# Boost_Converter.net
KiCad netlist of a schematic drawn in Altium Designer
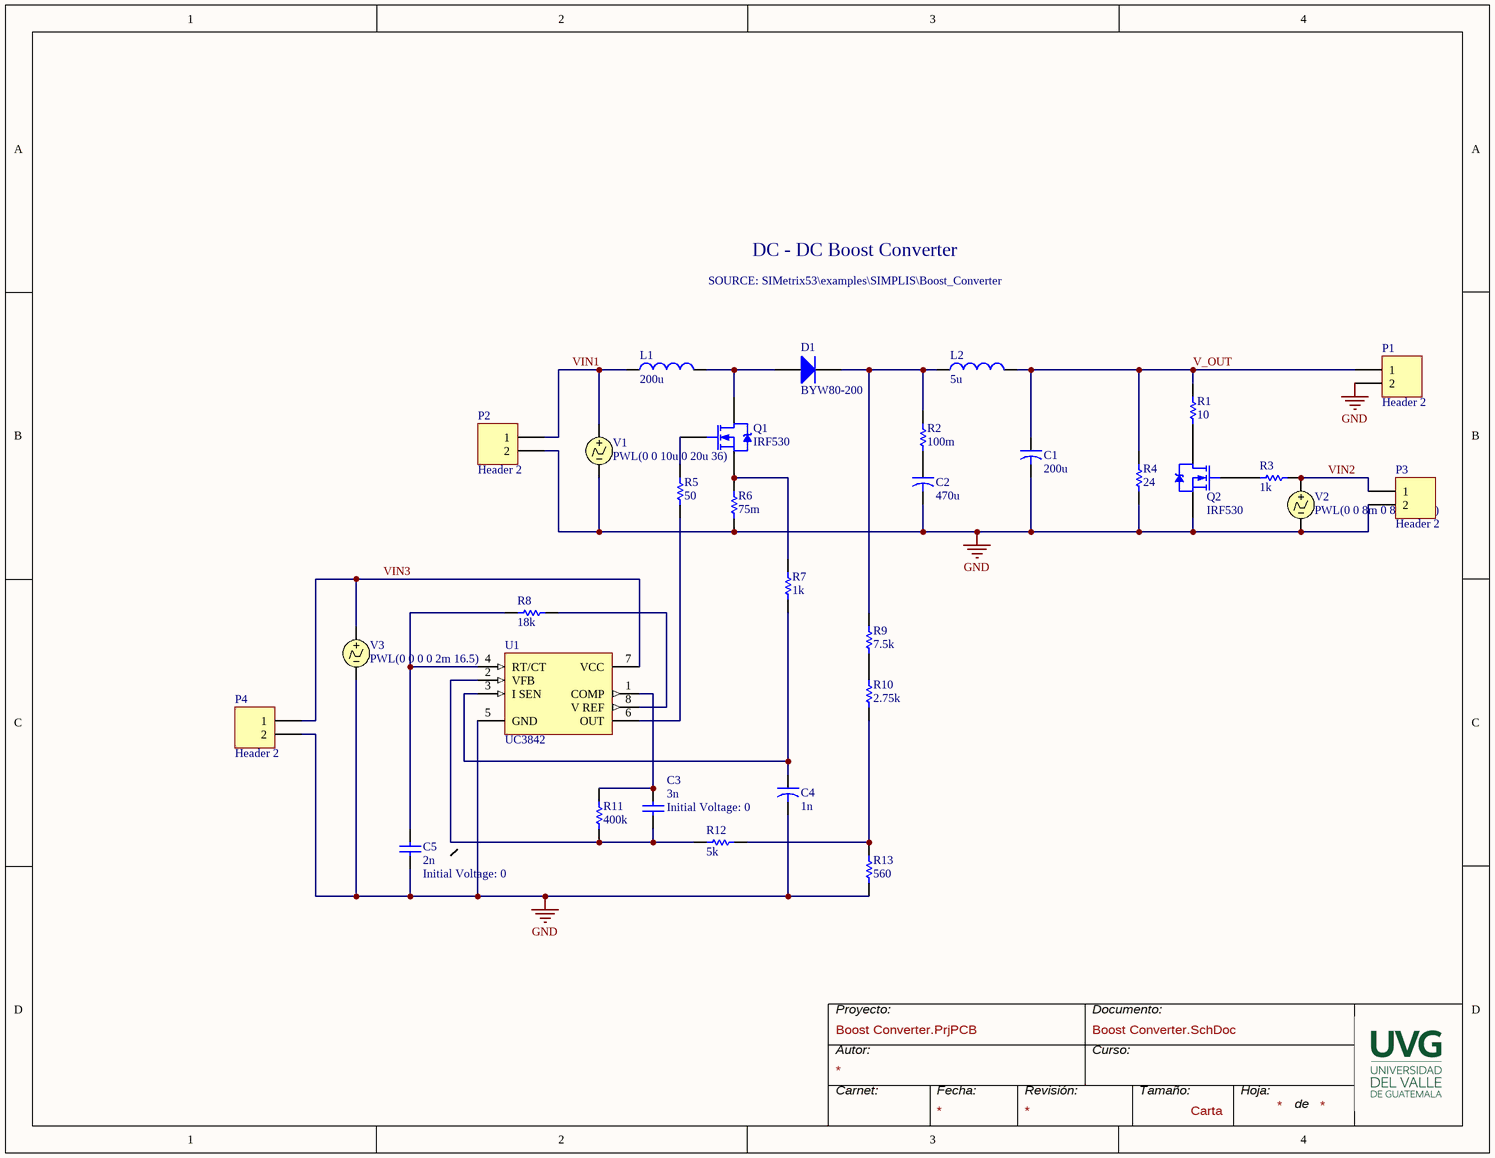
[diagram p0: Boost Converter.SchDoc]

(export (version "E")
  (design (tool "Eeschema 10.0.6"))
  (components
    (comp (ref "C1")
      (value "Cap Elec (L1-3)")
      (footprint "CAPR5-4X5")
      (description "Electrolytic Capacitor (Levels 1-3)")
      (fields (field (name "CC") "200u") (field (name "PUBLISHER") "Altium Limited"))
      (libsource (lib "SIMetrix Devices") (part "Cap Elec (L1-3)"))
    )
    (comp (ref "C2")
      (value "Cap Elec (L1-3)")
      (footprint "CAPR5-4X5")
      (description "Electrolytic Capacitor (Levels 1-3)")
      (fields (field (name "CC") "470u") (field (name "PUBLISHER") "Altium Limited"))
      (libsource (lib "SIMetrix Devices") (part "Cap Elec (L1-3)"))
    )
    (comp (ref "C3")
      (value "3n")
      (footprint "RAD-0.1")
      (description "Capacitor")
      (fields
        (field (name "INITIAL VOLTAGE") "0")
        (field (name "Comment") "Cap")
        (field (name "PUBLISHER") "Altium Limited")
      )
      (libsource (lib "Miscellaneous Devices") (part "Cap"))
    )
    (comp (ref "C4")
      (value "Cap Elec (L1-3)")
      (footprint "CAPR5-4X5")
      (description "Electrolytic Capacitor (Levels 1-3)")
      (fields (field (name "CC") "1n") (field (name "PUBLISHER") "Altium Limited"))
      (libsource (lib "SIMetrix Devices") (part "Cap Elec (L1-3)"))
    )
    (comp (ref "C5")
      (value "2n")
      (footprint "RAD-0.1")
      (description "Capacitor")
      (fields
        (field (name "INITIAL VOLTAGE") "0")
        (field (name "Comment") "Cap")
        (field (name "PUBLISHER") "Altium Limited")
      )
      (libsource (lib "Miscellaneous Devices") (part "Cap"))
    )
    (comp (ref "D1")
      (value "BYW80-200")
      (footprint "SMC")
      (description "High-Efficiency Fast Recovery Rectifier Diode")
      (fields (field (name "PUBLISHER") "Altium Limited"))
      (libsource (lib "SIMetrix Devices") (part "BYW80-200"))
    )
    (comp (ref "L1")
      (value "200u")
      (footprint "RAD")
      (description "Lossy Inductor")
      (fields (field (name "PUBLISHER") "Altium Limited"))
      (libsource (lib "SIMetrix Devices") (part "Inductor (Lossy)"))
    )
    (comp (ref "L2")
      (value "5u")
      (footprint "0402-A")
      (description "Lossy Inductor")
      (fields (field (name "PUBLISHER") "Altium Limited"))
      (libsource (lib "SIMetrix Devices") (part "Inductor (Lossy)"))
    )
    (comp (ref "P1")
      (value "Header 2")
      (footprint "HDR1X2")
      (description "Header, 2-Pin")
      (fields (field (name "PUBLISHER") "Altium Limited"))
      (libsource (lib "") (part "Header 2_1"))
    )
    (comp (ref "P2")
      (value "Header 2")
      (footprint "HDR1X2")
      (description "Header, 2-Pin")
      (fields (field (name "PUBLISHER") "Altium Limited"))
      (libsource (lib "Miscellaneous Connectors") (part "Header 2"))
    )
    (comp (ref "P3")
      (value "Header 2")
      (footprint "HDR1X2")
      (description "Header, 2-Pin")
      (fields (field (name "PUBLISHER") "Altium Limited"))
      (libsource (lib "") (part "Header 2_1"))
    )
    (comp (ref "P4")
      (value "Header 2")
      (footprint "HDR1X2")
      (description "Header, 2-Pin")
      (fields (field (name "PUBLISHER") "Altium Limited"))
      (libsource (lib "Miscellaneous Connectors") (part "Header 2"))
    )
    (comp (ref "Q1")
      (value "IRF530")
      (footprint "TO-220AB")
      (description "HEXFET N-Channel Power MOSFET")
      (fields (field (name "PUBLISHER") "Altium Limited"))
      (libsource (lib "SIMetrix Devices") (part "IRF530"))
    )
    (comp (ref "Q2")
      (value "IRF530")
      (footprint "TO-220AB")
      (description "HEXFET N-Channel Power MOSFET")
      (fields (field (name "PUBLISHER") "Altium Limited"))
      (libsource (lib "SIMetrix Devices") (part "IRF530"))
    )
    (comp (ref "R1")
      (value "10")
      (footprint "PCBComponent_1")
      (description "Resistor")
      (fields (field (name "Comment") "Res1") (field (name "PUBLISHER") "Altium Limited"))
      (libsource (lib "Miscellaneous Devices") (part "Res1"))
    )
    (comp (ref "R2")
      (value "100m")
      (footprint "PCBComponent_1")
      (description "Resistor")
      (fields (field (name "Comment") "Res1") (field (name "PUBLISHER") "Altium Limited"))
      (libsource (lib "Miscellaneous Devices") (part "Res1"))
    )
    (comp (ref "R3")
      (value "1k")
      (footprint "PCBComponent_1")
      (description "Resistor")
      (fields (field (name "Comment") "Res1") (field (name "PUBLISHER") "Altium Limited"))
      (libsource (lib "Miscellaneous Devices") (part "Res1"))
    )
    (comp (ref "R4")
      (value "24")
      (footprint "PCBComponent_1")
      (description "Resistor")
      (fields (field (name "Comment") "Res1") (field (name "PUBLISHER") "Altium Limited"))
      (libsource (lib "Miscellaneous Devices") (part "Res1"))
    )
    (comp (ref "R5")
      (value "50")
      (footprint "PCBComponent_1")
      (description "Resistor")
      (fields (field (name "Comment") "Res1") (field (name "PUBLISHER") "Altium Limited"))
      (libsource (lib "Miscellaneous Devices") (part "Res1"))
    )
    (comp (ref "R6")
      (value "75m")
      (footprint "PCBComponent_1")
      (description "Resistor")
      (fields (field (name "Comment") "Res1") (field (name "PUBLISHER") "Altium Limited"))
      (libsource (lib "Miscellaneous Devices") (part "Res1"))
    )
    (comp (ref "R7")
      (value "1k")
      (footprint "PCBComponent_1")
      (description "Resistor")
      (fields (field (name "Comment") "Res1") (field (name "PUBLISHER") "Altium Limited"))
      (libsource (lib "Miscellaneous Devices") (part "Res1"))
    )
    (comp (ref "R8")
      (value "18k")
      (footprint "PCBComponent_1")
      (description "Resistor")
      (fields (field (name "Comment") "Res1") (field (name "PUBLISHER") "Altium Limited"))
      (libsource (lib "Miscellaneous Devices") (part "Res1"))
    )
    (comp (ref "R9")
      (value "7.5k")
      (footprint "PCBComponent_1")
      (description "Resistor")
      (fields (field (name "Comment") "Res1") (field (name "PUBLISHER") "Altium Limited"))
      (libsource (lib "Miscellaneous Devices") (part "Res1"))
    )
    (comp (ref "R10")
      (value "2.75k")
      (footprint "PCBComponent_1")
      (description "Resistor")
      (fields (field (name "Comment") "Res1") (field (name "PUBLISHER") "Altium Limited"))
      (libsource (lib "Miscellaneous Devices") (part "Res1"))
    )
    (comp (ref "R11")
      (value "400k")
      (footprint "PCBComponent_1")
      (description "Resistor")
      (fields (field (name "Comment") "Res1") (field (name "PUBLISHER") "Altium Limited"))
      (libsource (lib "Miscellaneous Devices") (part "Res1"))
    )
    (comp (ref "R12")
      (value "5k")
      (footprint "PCBComponent_1")
      (description "Resistor")
      (fields (field (name "Comment") "Res1") (field (name "PUBLISHER") "Altium Limited"))
      (libsource (lib "Miscellaneous Devices") (part "Res1"))
    )
    (comp (ref "R13")
      (value "560")
      (footprint "PCBComponent_1")
      (description "Resistor")
      (fields (field (name "Comment") "Res1") (field (name "PUBLISHER") "Altium Limited"))
      (libsource (lib "Miscellaneous Devices") (part "Res1"))
    )
    (comp (ref "U1")
      (value "UC3842")
      (footprint "SO8_L")
      (description "High-Performance Current Mode PWM Controller")
      (fields (field (name "PUBLISHER") "Altium Limited"))
      (libsource (lib "SIMetrix Devices") (part "UC3842"))
    )
    (comp (ref "V1")
      (value "PWL(0 0 10u 0 20u 36)")
      (footprint "HDR1X2H")
      (description "Piecewise Linear Voltage Source")
      (fields (field (name "PUBLISHER") "Altium Limited"))
      (libsource (lib "Simulation Sources") (part "VPWL"))
    )
    (comp (ref "V2")
      (value "PWL(0 0 8m 0 8.01m 15)")
      (footprint "HDR1X2H")
      (description "Piecewise Linear Voltage Source")
      (fields (field (name "PUBLISHER") "Altium Limited"))
      (libsource (lib "Simulation Sources") (part "VPWL"))
    )
    (comp (ref "V3")
      (value "PWL(0 0 0 0 2m 16.5)")
      (footprint "HDR1X2H")
      (description "Piecewise Linear Voltage Source")
      (fields (field (name "PUBLISHER") "Altium Limited"))
      (libsource (lib "Simulation Sources") (part "VPWL"))
    )
  )
  (nets
    (net (code "1") (name "/VIN1") (class "Default")
      (node (ref "L1") (pin "1") (pinfunction "1_1") (pintype "passive"))
      (node (ref "P2") (pin "1") (pinfunction "1_1") (pintype "passive"))
      (node (ref "V1") (pin "1") (pinfunction "1_1") (pintype "passive"))
    )
    (net (code "2") (name "/VIN2") (class "Default")
      (node (ref "P3") (pin "1") (pinfunction "1_1") (pintype "passive"))
      (node (ref "R3") (pin "2") (pinfunction "2_2") (pintype "passive"))
      (node (ref "V2") (pin "1") (pinfunction "1_1") (pintype "passive"))
    )
    (net (code "3") (name "/VIN3") (class "Default")
      (node (ref "P4") (pin "1") (pinfunction "1_1") (pintype "passive"))
      (node (ref "U1") (pin "7") (pinfunction "VCC_7") (pintype "power_in"))
      (node (ref "V3") (pin "1") (pinfunction "1_1") (pintype "passive"))
    )
    (net (code "4") (name "/V_OUT") (class "Default")
      (node (ref "C1") (pin "1") (pinfunction "1_1") (pintype "passive"))
      (node (ref "L2") (pin "2") (pinfunction "2_2") (pintype "passive"))
      (node (ref "P1") (pin "1") (pinfunction "1_1") (pintype "passive"))
      (node (ref "R1") (pin "1") (pinfunction "1_1") (pintype "passive"))
      (node (ref "R4") (pin "1") (pinfunction "1_1") (pintype "passive"))
    )
    (net (code "5") (name "GND") (class "Default")
      (node (ref "C1") (pin "2") (pinfunction "2_2") (pintype "passive"))
      (node (ref "C2") (pin "2") (pinfunction "2_2") (pintype "passive"))
      (node (ref "C4") (pin "2") (pinfunction "2_2") (pintype "passive"))
      (node (ref "C5") (pin "2") (pinfunction "2_2") (pintype "passive"))
      (node (ref "P1") (pin "2") (pinfunction "2_2") (pintype "passive"))
      (node (ref "P2") (pin "2") (pinfunction "2_2") (pintype "passive"))
      (node (ref "P3") (pin "2") (pinfunction "2_2") (pintype "passive"))
      (node (ref "P4") (pin "2") (pinfunction "2_2") (pintype "passive"))
      (node (ref "Q2") (pin "3") (pinfunction "S_3") (pintype "passive"))
      (node (ref "R13") (pin "1") (pinfunction "1_1") (pintype "passive"))
      (node (ref "R4") (pin "2") (pinfunction "2_2") (pintype "passive"))
      (node (ref "R6") (pin "1") (pinfunction "1_1") (pintype "passive"))
      (node (ref "U1") (pin "5") (pinfunction "GND_5") (pintype "power_in"))
      (node (ref "V1") (pin "2") (pinfunction "2_2") (pintype "passive"))
      (node (ref "V2") (pin "2") (pinfunction "2_2") (pintype "passive"))
      (node (ref "V3") (pin "2") (pinfunction "2_2") (pintype "passive"))
    )
    (net (code "6") (name "Net-(C2-Pad1)") (class "Default")
      (node (ref "C2") (pin "1") (pinfunction "1_1") (pintype "passive"))
      (node (ref "R2") (pin "1") (pinfunction "1_1") (pintype "passive"))
    )
    (net (code "7") (name "Net-(D1-A)") (class "Default")
      (node (ref "D1") (pin "1") (pinfunction "A_1") (pintype "passive"))
      (node (ref "L1") (pin "2") (pinfunction "2_2") (pintype "passive"))
      (node (ref "Q1") (pin "2") (pinfunction "D_2") (pintype "passive"))
    )
    (net (code "8") (name "Net-(D1-K)") (class "Default")
      (node (ref "D1") (pin "2") (pinfunction "K_2") (pintype "passive"))
      (node (ref "L2") (pin "1") (pinfunction "1_1") (pintype "passive"))
      (node (ref "R2") (pin "2") (pinfunction "2_2") (pintype "passive"))
      (node (ref "R9") (pin "2") (pinfunction "2_2") (pintype "passive"))
    )
    (net (code "9") (name "Net-(Q1-G)") (class "Default")
      (node (ref "Q1") (pin "1") (pinfunction "G_1") (pintype "passive"))
      (node (ref "R5") (pin "2") (pinfunction "2_2") (pintype "passive"))
    )
    (net (code "10") (name "Net-(Q1-S)") (class "Default")
      (node (ref "Q1") (pin "3") (pinfunction "S_3") (pintype "passive"))
      (node (ref "R6") (pin "2") (pinfunction "2_2") (pintype "passive"))
      (node (ref "R7") (pin "2") (pinfunction "2_2") (pintype "passive"))
    )
    (net (code "11") (name "Net-(Q2-D)") (class "Default")
      (node (ref "Q2") (pin "2") (pinfunction "D_2") (pintype "passive"))
      (node (ref "R1") (pin "2") (pinfunction "2_2") (pintype "passive"))
    )
    (net (code "12") (name "Net-(Q2-G)") (class "Default")
      (node (ref "Q2") (pin "1") (pinfunction "G_1") (pintype "passive"))
      (node (ref "R3") (pin "1") (pinfunction "1_1") (pintype "passive"))
    )
    (net (code "13") (name "Net-(R10-Pad1)") (class "Default")
      (node (ref "R10") (pin "1") (pinfunction "1_1") (pintype "passive"))
      (node (ref "R12") (pin "1") (pinfunction "1_1") (pintype "passive"))
      (node (ref "R13") (pin "2") (pinfunction "2_2") (pintype "passive"))
    )
    (net (code "14") (name "Net-(R10-Pad2)") (class "Default")
      (node (ref "R10") (pin "2") (pinfunction "2_2") (pintype "passive"))
      (node (ref "R9") (pin "1") (pinfunction "1_1") (pintype "passive"))
    )
    (net (code "15") (name "Net-(U1-COMP)") (class "Default")
      (node (ref "C3") (pin "1") (pinfunction "1_1") (pintype "passive"))
      (node (ref "R11") (pin "2") (pinfunction "2_2") (pintype "passive"))
      (node (ref "U1") (pin "1") (pinfunction "COMP_1") (pintype "output"))
    )
    (net (code "16") (name "Net-(U1-I_SEN)") (class "Default")
      (node (ref "C4") (pin "1") (pinfunction "1_1") (pintype "passive"))
      (node (ref "R7") (pin "1") (pinfunction "1_1") (pintype "passive"))
      (node (ref "U1") (pin "3") (pinfunction "I_SEN_3") (pintype "input"))
    )
    (net (code "17") (name "Net-(U1-OUT)") (class "Default")
      (node (ref "R5") (pin "1") (pinfunction "1_1") (pintype "passive"))
      (node (ref "U1") (pin "6") (pinfunction "OUT_6") (pintype "tri_state"))
    )
    (net (code "18") (name "Net-(U1-RT{slash}CT)") (class "Default")
      (node (ref "C5") (pin "1") (pinfunction "1_1") (pintype "passive"))
      (node (ref "R8") (pin "2") (pinfunction "2_2") (pintype "passive"))
      (node (ref "U1") (pin "4") (pinfunction "RT/CT_4") (pintype "input"))
    )
    (net (code "19") (name "Net-(U1-VFB)") (class "Default")
      (node (ref "C3") (pin "2") (pinfunction "2_2") (pintype "passive"))
      (node (ref "R11") (pin "1") (pinfunction "1_1") (pintype "passive"))
      (node (ref "R12") (pin "2") (pinfunction "2_2") (pintype "passive"))
      (node (ref "U1") (pin "2") (pinfunction "VFB_2") (pintype "input"))
    )
    (net (code "20") (name "Net-(U1-V_REF)") (class "Default")
      (node (ref "R8") (pin "1") (pinfunction "1_1") (pintype "passive"))
      (node (ref "U1") (pin "8") (pinfunction "V_REF_8") (pintype "output"))
    )
  )
)
